# main.net
KiCad netlist of a schematic drawn in EAGLE
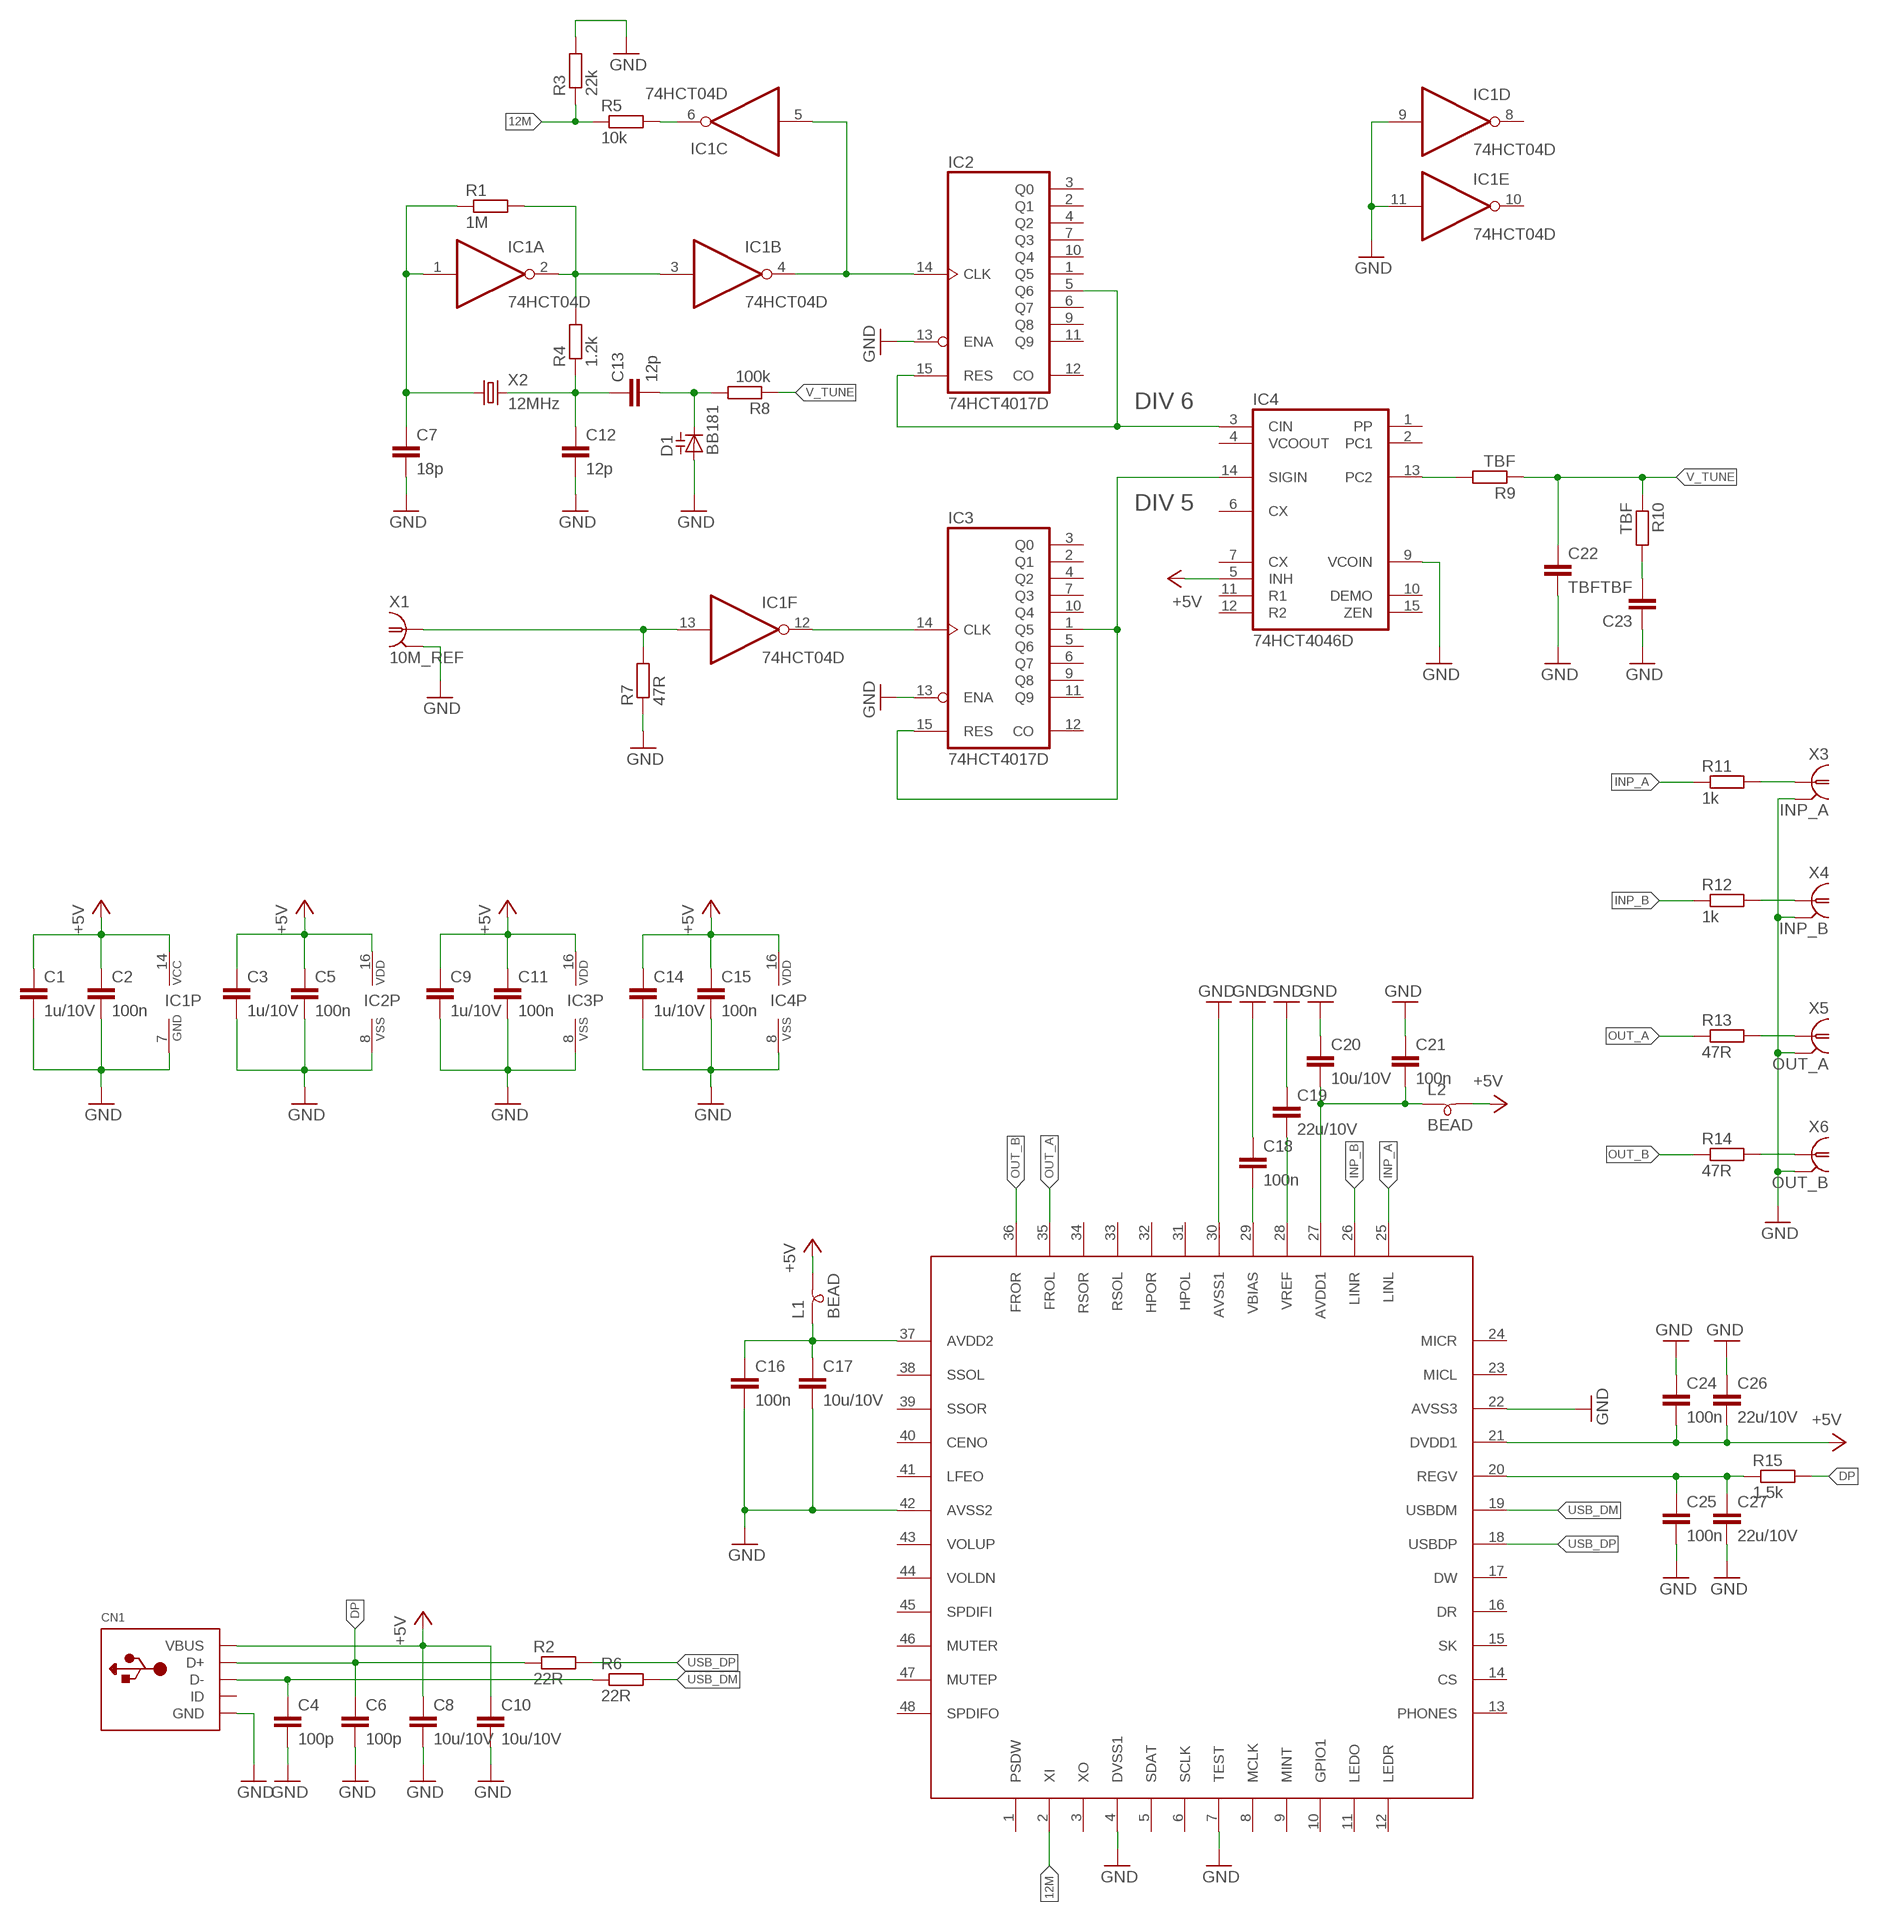
[diagram p0: schematic, sheet 1]

(export (version "E")
  (design (tool "Eeschema 10.0.6"))
  (components
    (comp (ref "C1")
      (value "1u/10V")
      (footprint "eagle-import:C0805")
      (libsource (lib "eagle-import") (part "C-EUC0805"))
    )
    (comp (ref "C2")
      (value "100n")
      (footprint "eagle-import:C0805")
      (libsource (lib "eagle-import") (part "C-EUC0805"))
    )
    (comp (ref "C3")
      (value "1u/10V")
      (footprint "eagle-import:C0805")
      (libsource (lib "eagle-import") (part "C-EUC0805"))
    )
    (comp (ref "C4")
      (value "100p")
      (footprint "eagle-import:C0805")
      (libsource (lib "eagle-import") (part "C-EUC0805"))
    )
    (comp (ref "C5")
      (value "100n")
      (footprint "eagle-import:C0805")
      (libsource (lib "eagle-import") (part "C-EUC0805"))
    )
    (comp (ref "C6")
      (value "100p")
      (footprint "eagle-import:C0805")
      (libsource (lib "eagle-import") (part "C-EUC0805"))
    )
    (comp (ref "C7")
      (value "18p")
      (footprint "eagle-import:C0805")
      (libsource (lib "eagle-import") (part "C-EUC0805"))
    )
    (comp (ref "C8")
      (value "10u/10V")
      (footprint "eagle-import:C1206")
      (libsource (lib "eagle-import") (part "C-EUC1206"))
    )
    (comp (ref "C9")
      (value "1u/10V")
      (footprint "eagle-import:C0805")
      (libsource (lib "eagle-import") (part "C-EUC0805"))
    )
    (comp (ref "C10")
      (value "10u/10V")
      (footprint "eagle-import:C1206")
      (libsource (lib "eagle-import") (part "C-EUC1206"))
    )
    (comp (ref "C11")
      (value "100n")
      (footprint "eagle-import:C0805")
      (libsource (lib "eagle-import") (part "C-EUC0805"))
    )
    (comp (ref "C12")
      (value "12p")
      (footprint "eagle-import:C0805")
      (libsource (lib "eagle-import") (part "C-EUC0805"))
    )
    (comp (ref "C13")
      (value "12p")
      (footprint "eagle-import:C0805")
      (libsource (lib "eagle-import") (part "C-EUC0805"))
    )
    (comp (ref "C14")
      (value "1u/10V")
      (footprint "eagle-import:C0805")
      (libsource (lib "eagle-import") (part "C-EUC0805"))
    )
    (comp (ref "C15")
      (value "100n")
      (footprint "eagle-import:C0805")
      (libsource (lib "eagle-import") (part "C-EUC0805"))
    )
    (comp (ref "C16")
      (value "100n")
      (footprint "eagle-import:C0805")
      (libsource (lib "eagle-import") (part "C-EUC0805"))
    )
    (comp (ref "C17")
      (value "10u/10V")
      (footprint "eagle-import:C0805")
      (libsource (lib "eagle-import") (part "C-EUC0805"))
    )
    (comp (ref "C18")
      (value "100n")
      (footprint "eagle-import:C0805")
      (libsource (lib "eagle-import") (part "C-EUC0805"))
    )
    (comp (ref "C19")
      (value "22u/10V")
      (footprint "eagle-import:C0805")
      (libsource (lib "eagle-import") (part "C-EUC0805"))
    )
    (comp (ref "C20")
      (value "10u/10V")
      (footprint "eagle-import:C0805")
      (libsource (lib "eagle-import") (part "C-EUC0805"))
    )
    (comp (ref "C21")
      (value "100n")
      (footprint "eagle-import:C0805")
      (libsource (lib "eagle-import") (part "C-EUC0805"))
    )
    (comp (ref "C22")
      (value "TBF")
      (footprint "eagle-import:C0805")
      (libsource (lib "eagle-import") (part "C-EUC0805"))
    )
    (comp (ref "C23")
      (value "TBF")
      (footprint "eagle-import:C0805")
      (libsource (lib "eagle-import") (part "C-EUC0805"))
    )
    (comp (ref "C24")
      (value "100n")
      (footprint "eagle-import:C0805")
      (libsource (lib "eagle-import") (part "C-EUC0805"))
    )
    (comp (ref "C25")
      (value "100n")
      (footprint "eagle-import:C0805")
      (libsource (lib "eagle-import") (part "C-EUC0805"))
    )
    (comp (ref "C26")
      (value "22u/10V")
      (footprint "eagle-import:C0805")
      (libsource (lib "eagle-import") (part "C-EUC0805"))
    )
    (comp (ref "C27")
      (value "22u/10V")
      (footprint "eagle-import:C0805")
      (libsource (lib "eagle-import") (part "C-EUC0805"))
    )
    (comp (ref "CN1")
      (value "USBMINIB")
      (footprint "eagle-import:USB-MINIB")
      (libsource (lib "eagle-import") (part "USBMINIB"))
    )
    (comp (ref "D1")
      (value "BB181")
      (footprint "eagle-import:SOD523")
      (libsource (lib "eagle-import") (part "BB141"))
    )
    (comp (ref "IC1")
      (value "74HCT04D")
      (footprint "eagle-import:SO14")
      (libsource (lib "eagle-import") (part "7404DHCT"))
    )
    (comp (ref "IC2")
      (value "74HCT4017D")
      (footprint "eagle-import:SO16")
      (libsource (lib "eagle-import") (part "4017D"))
    )
    (comp (ref "IC3")
      (value "74HCT4017D")
      (footprint "eagle-import:SO16")
      (libsource (lib "eagle-import") (part "4017D"))
    )
    (comp (ref "IC4")
      (value "74HCT4046D")
      (footprint "eagle-import:SO16")
      (libsource (lib "eagle-import") (part "4046D"))
    )
    (comp (ref "L1")
      (value "BEAD")
      (footprint "eagle-import:SM-B5")
      (libsource (lib "eagle-import") (part "SM-B5"))
    )
    (comp (ref "L2")
      (value "BEAD")
      (footprint "eagle-import:SM-B5")
      (libsource (lib "eagle-import") (part "SM-B5"))
    )
    (comp (ref "R1")
      (value "1M")
      (footprint "eagle-import:R0805")
      (libsource (lib "eagle-import") (part "R-EU_R0805"))
    )
    (comp (ref "R2")
      (value "22R")
      (footprint "eagle-import:R0805")
      (libsource (lib "eagle-import") (part "R-EU_R0805"))
    )
    (comp (ref "R3")
      (value "22k")
      (footprint "eagle-import:R0805")
      (libsource (lib "eagle-import") (part "R-EU_R0805"))
    )
    (comp (ref "R4")
      (value "1.2k")
      (footprint "eagle-import:R0805")
      (libsource (lib "eagle-import") (part "R-EU_R0805"))
    )
    (comp (ref "R5")
      (value "10k")
      (footprint "eagle-import:R0805")
      (libsource (lib "eagle-import") (part "R-EU_R0805"))
    )
    (comp (ref "R6")
      (value "22R")
      (footprint "eagle-import:R0805")
      (libsource (lib "eagle-import") (part "R-EU_R0805"))
    )
    (comp (ref "R7")
      (value "47R")
      (footprint "eagle-import:R0805")
      (libsource (lib "eagle-import") (part "R-EU_R0805"))
    )
    (comp (ref "R8")
      (value "100k")
      (footprint "eagle-import:R0805")
      (libsource (lib "eagle-import") (part "R-EU_R0805"))
    )
    (comp (ref "R9")
      (value "TBF")
      (footprint "eagle-import:R0805")
      (libsource (lib "eagle-import") (part "R-EU_R0805"))
    )
    (comp (ref "R10")
      (value "TBF")
      (footprint "eagle-import:R0805")
      (libsource (lib "eagle-import") (part "R-EU_R0805"))
    )
    (comp (ref "R11")
      (value "1k")
      (footprint "eagle-import:R0805")
      (libsource (lib "eagle-import") (part "R-EU_R0805"))
    )
    (comp (ref "R12")
      (value "1k")
      (footprint "eagle-import:R0805")
      (libsource (lib "eagle-import") (part "R-EU_R0805"))
    )
    (comp (ref "R13")
      (value "47R")
      (footprint "eagle-import:R0805")
      (libsource (lib "eagle-import") (part "R-EU_R0805"))
    )
    (comp (ref "R14")
      (value "47R")
      (footprint "eagle-import:R0805")
      (libsource (lib "eagle-import") (part "R-EU_R0805"))
    )
    (comp (ref "R15")
      (value "1.5k")
      (footprint "eagle-import:R0805")
      (libsource (lib "eagle-import") (part "R-EU_R0805"))
    )
    (comp (ref "U1")
      (value "CM6206")
      (footprint "eagle-import:LQFP-48")
      (libsource (lib "eagle-import") (part "CM6206"))
    )
    (comp (ref "X1")
      (value "10M_REF")
      (footprint "eagle-import:AMP_227161")
      (libsource (lib "eagle-import") (part "?2271611--2"))
    )
    (comp (ref "X2")
      (value "12MHz")
      (footprint "eagle-import:HC49")
      (libsource (lib "eagle-import") (part "CRYSTALS-NOGND-HC49/4H"))
    )
    (comp (ref "X3")
      (value "INP_A")
      (footprint "eagle-import:AMP_227161")
      (libsource (lib "eagle-import") (part "?2271611--2"))
    )
    (comp (ref "X4")
      (value "INP_B")
      (footprint "eagle-import:AMP_227161")
      (libsource (lib "eagle-import") (part "?2271611--2"))
    )
    (comp (ref "X5")
      (value "OUT_A")
      (footprint "eagle-import:AMP_227161")
      (libsource (lib "eagle-import") (part "?2271611--2"))
    )
    (comp (ref "X6")
      (value "OUT_B")
      (footprint "eagle-import:AMP_227161")
      (libsource (lib "eagle-import") (part "?2271611--2"))
    )
  )
  (nets
    (net (code "1") (name "+5V") (class "Default")
      (node (ref "C1") (pin "1") (pinfunction "1_1") (pintype "passive"))
      (node (ref "C10") (pin "1") (pinfunction "1_1") (pintype "passive"))
      (node (ref "C11") (pin "1") (pinfunction "1_1") (pintype "passive"))
      (node (ref "C14") (pin "1") (pinfunction "1_1") (pintype "passive"))
      (node (ref "C15") (pin "1") (pinfunction "1_1") (pintype "passive"))
      (node (ref "C2") (pin "1") (pinfunction "1_1") (pintype "passive"))
      (node (ref "C24") (pin "2") (pinfunction "2_2") (pintype "passive"))
      (node (ref "C26") (pin "2") (pinfunction "2_2") (pintype "passive"))
      (node (ref "C3") (pin "1") (pinfunction "1_1") (pintype "passive"))
      (node (ref "C5") (pin "1") (pinfunction "1_1") (pintype "passive"))
      (node (ref "C8") (pin "1") (pinfunction "1_1") (pintype "passive"))
      (node (ref "C9") (pin "1") (pinfunction "1_1") (pintype "passive"))
      (node (ref "CN1") (pin "VBUS") (pinfunction "VBUS_VBUS") (pintype "power_in"))
      (node (ref "IC1") (pin "14") (pinfunction "VCC_14") (pintype "power_in"))
      (node (ref "IC2") (pin "16") (pinfunction "VDD_16") (pintype "power_in"))
      (node (ref "IC3") (pin "16") (pinfunction "VDD_16") (pintype "power_in"))
      (node (ref "IC4") (pin "16") (pinfunction "VDD_16") (pintype "power_in"))
      (node (ref "IC4") (pin "5") (pinfunction "INH_5") (pintype "input"))
      (node (ref "L1") (pin "2") (pinfunction "2_2") (pintype "passive"))
      (node (ref "L2") (pin "2") (pinfunction "2_2") (pintype "passive"))
      (node (ref "U1") (pin "21") (pinfunction "DVDD1_21") (pintype "bidirectional"))
    )
    (net (code "2") (name "12M") (class "Default")
      (node (ref "R3") (pin "1") (pinfunction "1_1") (pintype "passive"))
      (node (ref "R5") (pin "1") (pinfunction "1_1") (pintype "passive"))
      (node (ref "U1") (pin "2") (pinfunction "XI_2") (pintype "bidirectional"))
    )
    (net (code "3") (name "DP") (class "Default")
      (node (ref "C6") (pin "1") (pinfunction "1_1") (pintype "passive"))
      (node (ref "CN1") (pin "D+") (pinfunction "D+_D+") (pintype "bidirectional"))
      (node (ref "R15") (pin "2") (pinfunction "2_2") (pintype "passive"))
      (node (ref "R2") (pin "1") (pinfunction "1_1") (pintype "passive"))
    )
    (net (code "4") (name "GND") (class "Default")
      (node (ref "C1") (pin "2") (pinfunction "2_2") (pintype "passive"))
      (node (ref "C10") (pin "2") (pinfunction "2_2") (pintype "passive"))
      (node (ref "C11") (pin "2") (pinfunction "2_2") (pintype "passive"))
      (node (ref "C12") (pin "2") (pinfunction "2_2") (pintype "passive"))
      (node (ref "C14") (pin "2") (pinfunction "2_2") (pintype "passive"))
      (node (ref "C15") (pin "2") (pinfunction "2_2") (pintype "passive"))
      (node (ref "C16") (pin "2") (pinfunction "2_2") (pintype "passive"))
      (node (ref "C17") (pin "2") (pinfunction "2_2") (pintype "passive"))
      (node (ref "C18") (pin "1") (pinfunction "1_1") (pintype "passive"))
      (node (ref "C19") (pin "1") (pinfunction "1_1") (pintype "passive"))
      (node (ref "C2") (pin "2") (pinfunction "2_2") (pintype "passive"))
      (node (ref "C20") (pin "1") (pinfunction "1_1") (pintype "passive"))
      (node (ref "C21") (pin "1") (pinfunction "1_1") (pintype "passive"))
      (node (ref "C22") (pin "2") (pinfunction "2_2") (pintype "passive"))
      (node (ref "C23") (pin "1") (pinfunction "1_1") (pintype "passive"))
      (node (ref "C24") (pin "1") (pinfunction "1_1") (pintype "passive"))
      (node (ref "C25") (pin "2") (pinfunction "2_2") (pintype "passive"))
      (node (ref "C26") (pin "1") (pinfunction "1_1") (pintype "passive"))
      (node (ref "C27") (pin "2") (pinfunction "2_2") (pintype "passive"))
      (node (ref "C3") (pin "2") (pinfunction "2_2") (pintype "passive"))
      (node (ref "C4") (pin "2") (pinfunction "2_2") (pintype "passive"))
      (node (ref "C5") (pin "2") (pinfunction "2_2") (pintype "passive"))
      (node (ref "C6") (pin "2") (pinfunction "2_2") (pintype "passive"))
      (node (ref "C7") (pin "2") (pinfunction "2_2") (pintype "passive"))
      (node (ref "C8") (pin "2") (pinfunction "2_2") (pintype "passive"))
      (node (ref "C9") (pin "2") (pinfunction "2_2") (pintype "passive"))
      (node (ref "CN1") (pin "GND") (pinfunction "GND_GND") (pintype "power_in"))
      (node (ref "D1") (pin "A") (pinfunction "A_A") (pintype "passive"))
      (node (ref "IC1") (pin "11") (pinfunction "I_11") (pintype "input"))
      (node (ref "IC1") (pin "7") (pinfunction "GND_7") (pintype "power_in"))
      (node (ref "IC1") (pin "9") (pinfunction "I_9") (pintype "input"))
      (node (ref "IC2") (pin "13") (pinfunction "ENA_13") (pintype "input"))
      (node (ref "IC2") (pin "8") (pinfunction "VSS_8") (pintype "power_in"))
      (node (ref "IC3") (pin "13") (pinfunction "ENA_13") (pintype "input"))
      (node (ref "IC3") (pin "8") (pinfunction "VSS_8") (pintype "power_in"))
      (node (ref "IC4") (pin "8") (pinfunction "VSS_8") (pintype "power_in"))
      (node (ref "IC4") (pin "9") (pinfunction "VCOIN_9") (pintype "input"))
      (node (ref "R3") (pin "2") (pinfunction "2_2") (pintype "passive"))
      (node (ref "R7") (pin "1") (pinfunction "1_1") (pintype "passive"))
      (node (ref "U1") (pin "22") (pinfunction "AVSS3_22") (pintype "bidirectional"))
      (node (ref "U1") (pin "30") (pinfunction "AVSS1_30") (pintype "bidirectional"))
      (node (ref "U1") (pin "4") (pinfunction "DVSS1_4") (pintype "bidirectional"))
      (node (ref "U1") (pin "42") (pinfunction "AVSS2_42") (pintype "bidirectional"))
      (node (ref "U1") (pin "7") (pinfunction "TEST_7") (pintype "bidirectional"))
      (node (ref "X1") (pin "2") (pinfunction "2_2") (pintype "passive"))
      (node (ref "X3") (pin "2") (pinfunction "2_2") (pintype "passive"))
      (node (ref "X4") (pin "2") (pinfunction "2_2") (pintype "passive"))
      (node (ref "X5") (pin "2") (pinfunction "2_2") (pintype "passive"))
      (node (ref "X6") (pin "2") (pinfunction "2_2") (pintype "passive"))
    )
    (net (code "5") (name "INP_A") (class "Default")
      (node (ref "R11") (pin "1") (pinfunction "1_1") (pintype "passive"))
      (node (ref "U1") (pin "25") (pinfunction "LINL_25") (pintype "bidirectional"))
    )
    (net (code "6") (name "INP_B") (class "Default")
      (node (ref "R12") (pin "1") (pinfunction "1_1") (pintype "passive"))
      (node (ref "U1") (pin "26") (pinfunction "LINR_26") (pintype "bidirectional"))
    )
    (net (code "7") (name "Net-(C4-Pad1)") (class "Default")
      (node (ref "C4") (pin "1") (pinfunction "1_1") (pintype "passive"))
      (node (ref "CN1") (pin "D-") (pinfunction "D-_D-") (pintype "bidirectional"))
      (node (ref "R6") (pin "1") (pinfunction "1_1") (pintype "passive"))
    )
    (net (code "8") (name "Net-(C12-Pad1)") (class "Default")
      (node (ref "C12") (pin "1") (pinfunction "1_1") (pintype "passive"))
      (node (ref "C13") (pin "1") (pinfunction "1_1") (pintype "passive"))
      (node (ref "R4") (pin "1") (pinfunction "1_1") (pintype "passive"))
      (node (ref "X2") (pin "2") (pinfunction "2_2") (pintype "passive"))
    )
    (net (code "9") (name "Net-(C13-Pad2)") (class "Default")
      (node (ref "C13") (pin "2") (pinfunction "2_2") (pintype "passive"))
      (node (ref "D1") (pin "C") (pinfunction "C_C") (pintype "passive"))
      (node (ref "R8") (pin "2") (pinfunction "2_2") (pintype "passive"))
    )
    (net (code "10") (name "Net-(C23-Pad2)") (class "Default")
      (node (ref "C23") (pin "2") (pinfunction "2_2") (pintype "passive"))
      (node (ref "R10") (pin "2") (pinfunction "2_2") (pintype "passive"))
    )
    (net (code "11") (name "Net-(IC1A-I)") (class "Default")
      (node (ref "C7") (pin "1") (pinfunction "1_1") (pintype "passive"))
      (node (ref "IC1") (pin "1") (pinfunction "I_1") (pintype "input"))
      (node (ref "R1") (pin "1") (pinfunction "1_1") (pintype "passive"))
      (node (ref "X2") (pin "1") (pinfunction "1_1") (pintype "passive"))
    )
    (net (code "12") (name "Net-(IC1A-O)") (class "Default")
      (node (ref "IC1") (pin "2") (pinfunction "O_2") (pintype "output"))
      (node (ref "IC1") (pin "3") (pinfunction "I_3") (pintype "input"))
      (node (ref "R1") (pin "2") (pinfunction "2_2") (pintype "passive"))
      (node (ref "R4") (pin "2") (pinfunction "2_2") (pintype "passive"))
    )
    (net (code "13") (name "Net-(IC1B-O)") (class "Default")
      (node (ref "IC1") (pin "4") (pinfunction "O_4") (pintype "output"))
      (node (ref "IC1") (pin "5") (pinfunction "I_5") (pintype "input"))
      (node (ref "IC2") (pin "14") (pinfunction "CLK_14") (pintype "input"))
    )
    (net (code "14") (name "Net-(IC1C-O)") (class "Default")
      (node (ref "IC1") (pin "6") (pinfunction "O_6") (pintype "output"))
      (node (ref "R5") (pin "2") (pinfunction "2_2") (pintype "passive"))
    )
    (net (code "15") (name "Net-(IC1F-I)") (class "Default")
      (node (ref "IC1") (pin "13") (pinfunction "I_13") (pintype "input"))
      (node (ref "R7") (pin "2") (pinfunction "2_2") (pintype "passive"))
      (node (ref "X1") (pin "1") (pinfunction "1_1") (pintype "passive"))
    )
    (net (code "16") (name "Net-(IC1F-O)") (class "Default")
      (node (ref "IC1") (pin "12") (pinfunction "O_12") (pintype "output"))
      (node (ref "IC3") (pin "14") (pinfunction "CLK_14") (pintype "input"))
    )
    (net (code "17") (name "Net-(IC2A-Q6)") (class "Default")
      (node (ref "IC2") (pin "15") (pinfunction "RES_15") (pintype "input"))
      (node (ref "IC2") (pin "5") (pinfunction "Q6_5") (pintype "output"))
      (node (ref "IC4") (pin "3") (pinfunction "CIN_3") (pintype "input"))
    )
    (net (code "18") (name "Net-(IC3A-Q5)") (class "Default")
      (node (ref "IC3") (pin "1") (pinfunction "Q5_1") (pintype "output"))
      (node (ref "IC3") (pin "15") (pinfunction "RES_15") (pintype "input"))
      (node (ref "IC4") (pin "14") (pinfunction "SIGIN_14") (pintype "input"))
    )
    (net (code "19") (name "Net-(IC4A-PC2)") (class "Default")
      (node (ref "IC4") (pin "13") (pinfunction "PC2_13") (pintype "output"))
      (node (ref "R9") (pin "2") (pinfunction "2_2") (pintype "passive"))
    )
    (net (code "20") (name "Net-(R11-Pad2)") (class "Default")
      (node (ref "R11") (pin "2") (pinfunction "2_2") (pintype "passive"))
      (node (ref "X3") (pin "1") (pinfunction "1_1") (pintype "passive"))
    )
    (net (code "21") (name "Net-(R12-Pad2)") (class "Default")
      (node (ref "R12") (pin "2") (pinfunction "2_2") (pintype "passive"))
      (node (ref "X4") (pin "1") (pinfunction "1_1") (pintype "passive"))
    )
    (net (code "22") (name "Net-(R13-Pad2)") (class "Default")
      (node (ref "R13") (pin "2") (pinfunction "2_2") (pintype "passive"))
      (node (ref "X5") (pin "1") (pinfunction "1_1") (pintype "passive"))
    )
    (net (code "23") (name "Net-(R14-Pad2)") (class "Default")
      (node (ref "R14") (pin "2") (pinfunction "2_2") (pintype "passive"))
      (node (ref "X6") (pin "1") (pinfunction "1_1") (pintype "passive"))
    )
    (net (code "24") (name "Net-(U1-AVDD1)") (class "Default")
      (node (ref "C20") (pin "2") (pinfunction "2_2") (pintype "passive"))
      (node (ref "C21") (pin "2") (pinfunction "2_2") (pintype "passive"))
      (node (ref "L2") (pin "1") (pinfunction "1_1") (pintype "passive"))
      (node (ref "U1") (pin "27") (pinfunction "AVDD1_27") (pintype "bidirectional"))
    )
    (net (code "25") (name "Net-(U1-AVDD2)") (class "Default")
      (node (ref "C16") (pin "1") (pinfunction "1_1") (pintype "passive"))
      (node (ref "C17") (pin "1") (pinfunction "1_1") (pintype "passive"))
      (node (ref "L1") (pin "1") (pinfunction "1_1") (pintype "passive"))
      (node (ref "U1") (pin "37") (pinfunction "AVDD2_37") (pintype "bidirectional"))
    )
    (net (code "26") (name "Net-(U1-REGV)") (class "Default")
      (node (ref "C25") (pin "1") (pinfunction "1_1") (pintype "passive"))
      (node (ref "C27") (pin "1") (pinfunction "1_1") (pintype "passive"))
      (node (ref "R15") (pin "1") (pinfunction "1_1") (pintype "passive"))
      (node (ref "U1") (pin "20") (pinfunction "REGV_20") (pintype "bidirectional"))
    )
    (net (code "27") (name "Net-(U1-VBIAS)") (class "Default")
      (node (ref "C18") (pin "2") (pinfunction "2_2") (pintype "passive"))
      (node (ref "U1") (pin "29") (pinfunction "VBIAS_29") (pintype "bidirectional"))
    )
    (net (code "28") (name "Net-(U1-VREF)") (class "Default")
      (node (ref "C19") (pin "2") (pinfunction "2_2") (pintype "passive"))
      (node (ref "U1") (pin "28") (pinfunction "VREF_28") (pintype "bidirectional"))
    )
    (net (code "29") (name "OUT_A") (class "Default")
      (node (ref "R13") (pin "1") (pinfunction "1_1") (pintype "passive"))
      (node (ref "U1") (pin "35") (pinfunction "FROL_35") (pintype "bidirectional"))
    )
    (net (code "30") (name "OUT_B") (class "Default")
      (node (ref "R14") (pin "1") (pinfunction "1_1") (pintype "passive"))
      (node (ref "U1") (pin "36") (pinfunction "FROR_36") (pintype "bidirectional"))
    )
    (net (code "31") (name "USB_DM") (class "Default")
      (node (ref "R6") (pin "2") (pinfunction "2_2") (pintype "passive"))
      (node (ref "U1") (pin "19") (pinfunction "USBDM_19") (pintype "bidirectional"))
    )
    (net (code "32") (name "USB_DP") (class "Default")
      (node (ref "R2") (pin "2") (pinfunction "2_2") (pintype "passive"))
      (node (ref "U1") (pin "18") (pinfunction "USBDP_18") (pintype "bidirectional"))
    )
    (net (code "33") (name "V_TUNE") (class "Default")
      (node (ref "C22") (pin "1") (pinfunction "1_1") (pintype "passive"))
      (node (ref "R10") (pin "1") (pinfunction "1_1") (pintype "passive"))
      (node (ref "R8") (pin "1") (pinfunction "1_1") (pintype "passive"))
      (node (ref "R9") (pin "1") (pinfunction "1_1") (pintype "passive"))
    )
    (net (code "34") (name "unconnected-(CN1-PadID)") (class "Default")
      (node (ref "CN1") (pin "ID") (pinfunction "ID_ID") (pintype "bidirectional"))
    )
    (net (code "35") (name "unconnected-(IC1D-O-Pad8)") (class "Default")
      (node (ref "IC1") (pin "8") (pinfunction "O_8") (pintype "output"))
    )
    (net (code "36") (name "unconnected-(IC1E-O-Pad10)") (class "Default")
      (node (ref "IC1") (pin "10") (pinfunction "O_10") (pintype "output"))
    )
    (net (code "37") (name "unconnected-(IC2A-CO-Pad12)") (class "Default")
      (node (ref "IC2") (pin "12") (pinfunction "CO_12") (pintype "output"))
    )
    (net (code "38") (name "unconnected-(IC2A-Q0-Pad3)") (class "Default")
      (node (ref "IC2") (pin "3") (pinfunction "Q0_3") (pintype "output"))
    )
    (net (code "39") (name "unconnected-(IC2A-Q1-Pad2)") (class "Default")
      (node (ref "IC2") (pin "2") (pinfunction "Q1_2") (pintype "output"))
    )
    (net (code "40") (name "unconnected-(IC2A-Q2-Pad4)") (class "Default")
      (node (ref "IC2") (pin "4") (pinfunction "Q2_4") (pintype "output"))
    )
    (net (code "41") (name "unconnected-(IC2A-Q3-Pad7)") (class "Default")
      (node (ref "IC2") (pin "7") (pinfunction "Q3_7") (pintype "output"))
    )
    (net (code "42") (name "unconnected-(IC2A-Q4-Pad10)") (class "Default")
      (node (ref "IC2") (pin "10") (pinfunction "Q4_10") (pintype "output"))
    )
    (net (code "43") (name "unconnected-(IC2A-Q5-Pad1)") (class "Default")
      (node (ref "IC2") (pin "1") (pinfunction "Q5_1") (pintype "output"))
    )
    (net (code "44") (name "unconnected-(IC2A-Q7-Pad6)") (class "Default")
      (node (ref "IC2") (pin "6") (pinfunction "Q7_6") (pintype "output"))
    )
    (net (code "45") (name "unconnected-(IC2A-Q8-Pad9)") (class "Default")
      (node (ref "IC2") (pin "9") (pinfunction "Q8_9") (pintype "output"))
    )
    (net (code "46") (name "unconnected-(IC2A-Q9-Pad11)") (class "Default")
      (node (ref "IC2") (pin "11") (pinfunction "Q9_11") (pintype "output"))
    )
    (net (code "47") (name "unconnected-(IC3A-CO-Pad12)") (class "Default")
      (node (ref "IC3") (pin "12") (pinfunction "CO_12") (pintype "output"))
    )
    (net (code "48") (name "unconnected-(IC3A-Q0-Pad3)") (class "Default")
      (node (ref "IC3") (pin "3") (pinfunction "Q0_3") (pintype "output"))
    )
    (net (code "49") (name "unconnected-(IC3A-Q1-Pad2)") (class "Default")
      (node (ref "IC3") (pin "2") (pinfunction "Q1_2") (pintype "output"))
    )
    (net (code "50") (name "unconnected-(IC3A-Q2-Pad4)") (class "Default")
      (node (ref "IC3") (pin "4") (pinfunction "Q2_4") (pintype "output"))
    )
    (net (code "51") (name "unconnected-(IC3A-Q3-Pad7)") (class "Default")
      (node (ref "IC3") (pin "7") (pinfunction "Q3_7") (pintype "output"))
    )
    (net (code "52") (name "unconnected-(IC3A-Q4-Pad10)") (class "Default")
      (node (ref "IC3") (pin "10") (pinfunction "Q4_10") (pintype "output"))
    )
    (net (code "53") (name "unconnected-(IC3A-Q6-Pad5)") (class "Default")
      (node (ref "IC3") (pin "5") (pinfunction "Q6_5") (pintype "output"))
    )
    (net (code "54") (name "unconnected-(IC3A-Q7-Pad6)") (class "Default")
      (node (ref "IC3") (pin "6") (pinfunction "Q7_6") (pintype "output"))
    )
    (net (code "55") (name "unconnected-(IC3A-Q8-Pad9)") (class "Default")
      (node (ref "IC3") (pin "9") (pinfunction "Q8_9") (pintype "output"))
    )
    (net (code "56") (name "unconnected-(IC3A-Q9-Pad11)") (class "Default")
      (node (ref "IC3") (pin "11") (pinfunction "Q9_11") (pintype "output"))
    )
    (net (code "57") (name "unconnected-(IC4A-CX-Pad6)") (class "Default")
      (node (ref "IC4") (pin "6") (pinfunction "CX_6") (pintype "input"))
    )
    (net (code "58") (name "unconnected-(IC4A-CX-Pad7)") (class "Default")
      (node (ref "IC4") (pin "7") (pinfunction "CX_7") (pintype "input"))
    )
    (net (code "59") (name "unconnected-(IC4A-DEMO-Pad10)") (class "Default")
      (node (ref "IC4") (pin "10") (pinfunction "DEMO_10") (pintype "output"))
    )
    (net (code "60") (name "unconnected-(IC4A-PC1-Pad2)") (class "Default")
      (node (ref "IC4") (pin "2") (pinfunction "PC1_2") (pintype "output"))
    )
    (net (code "61") (name "unconnected-(IC4A-PP-Pad1)") (class "Default")
      (node (ref "IC4") (pin "1") (pinfunction "PP_1") (pintype "output"))
    )
    (net (code "62") (name "unconnected-(IC4A-R1-Pad11)") (class "Default")
      (node (ref "IC4") (pin "11") (pinfunction "R1_11") (pintype "input"))
    )
    (net (code "63") (name "unconnected-(IC4A-R2-Pad12)") (class "Default")
      (node (ref "IC4") (pin "12") (pinfunction "R2_12") (pintype "input"))
    )
    (net (code "64") (name "unconnected-(IC4A-VCOOUT-Pad4)") (class "Default")
      (node (ref "IC4") (pin "4") (pinfunction "VCOOUT_4") (pintype "output"))
    )
    (net (code "65") (name "unconnected-(IC4A-ZEN-Pad15)") (class "Default")
      (node (ref "IC4") (pin "15") (pinfunction "ZEN_15") (pintype "input"))
    )
    (net (code "66") (name "unconnected-(U1-CENO-Pad40)") (class "Default")
      (node (ref "U1") (pin "40") (pinfunction "CENO_40") (pintype "bidirectional"))
    )
    (net (code "67") (name "unconnected-(U1-CS-Pad14)") (class "Default")
      (node (ref "U1") (pin "14") (pinfunction "CS_14") (pintype "bidirectional"))
    )
    (net (code "68") (name "unconnected-(U1-DR-Pad16)") (class "Default")
      (node (ref "U1") (pin "16") (pinfunction "DR_16") (pintype "bidirectional"))
    )
    (net (code "69") (name "unconnected-(U1-DW-Pad17)") (class "Default")
      (node (ref "U1") (pin "17") (pinfunction "DW_17") (pintype "bidirectional"))
    )
    (net (code "70") (name "unconnected-(U1-GPIO1-Pad10)") (class "Default")
      (node (ref "U1") (pin "10") (pinfunction "GPIO1_10") (pintype "bidirectional"))
    )
    (net (code "71") (name "unconnected-(U1-HPOL-Pad31)") (class "Default")
      (node (ref "U1") (pin "31") (pinfunction "HPOL_31") (pintype "bidirectional"))
    )
    (net (code "72") (name "unconnected-(U1-HPOR-Pad32)") (class "Default")
      (node (ref "U1") (pin "32") (pinfunction "HPOR_32") (pintype "bidirectional"))
    )
    (net (code "73") (name "unconnected-(U1-LEDO-Pad11)") (class "Default")
      (node (ref "U1") (pin "11") (pinfunction "LEDO_11") (pintype "bidirectional"))
    )
    (net (code "74") (name "unconnected-(U1-LEDR-Pad12)") (class "Default")
      (node (ref "U1") (pin "12") (pinfunction "LEDR_12") (pintype "bidirectional"))
    )
    (net (code "75") (name "unconnected-(U1-LFEO-Pad41)") (class "Default")
      (node (ref "U1") (pin "41") (pinfunction "LFEO_41") (pintype "bidirectional"))
    )
    (net (code "76") (name "unconnected-(U1-MCLK-Pad8)") (class "Default")
      (node (ref "U1") (pin "8") (pinfunction "MCLK_8") (pintype "bidirectional"))
    )
    (net (code "77") (name "unconnected-(U1-MICL-Pad23)") (class "Default")
      (node (ref "U1") (pin "23") (pinfunction "MICL_23") (pintype "bidirectional"))
    )
    (net (code "78") (name "unconnected-(U1-MICR-Pad24)") (class "Default")
      (node (ref "U1") (pin "24") (pinfunction "MICR_24") (pintype "bidirectional"))
    )
    (net (code "79") (name "unconnected-(U1-MINT-Pad9)") (class "Default")
      (node (ref "U1") (pin "9") (pinfunction "MINT_9") (pintype "bidirectional"))
    )
    (net (code "80") (name "unconnected-(U1-MUTEP-Pad47)") (class "Default")
      (node (ref "U1") (pin "47") (pinfunction "MUTEP_47") (pintype "bidirectional"))
    )
    (net (code "81") (name "unconnected-(U1-MUTER-Pad46)") (class "Default")
      (node (ref "U1") (pin "46") (pinfunction "MUTER_46") (pintype "bidirectional"))
    )
    (net (code "82") (name "unconnected-(U1-PHONES-Pad13)") (class "Default")
      (node (ref "U1") (pin "13") (pinfunction "PHONES_13") (pintype "bidirectional"))
    )
    (net (code "83") (name "unconnected-(U1-PSDW-Pad1)") (class "Default")
      (node (ref "U1") (pin "1") (pinfunction "PSDW_1") (pintype "bidirectional"))
    )
    (net (code "84") (name "unconnected-(U1-RSOL-Pad33)") (class "Default")
      (node (ref "U1") (pin "33") (pinfunction "RSOL_33") (pintype "bidirectional"))
    )
    (net (code "85") (name "unconnected-(U1-RSOR-Pad34)") (class "Default")
      (node (ref "U1") (pin "34") (pinfunction "RSOR_34") (pintype "bidirectional"))
    )
    (net (code "86") (name "unconnected-(U1-SCLK-Pad6)") (class "Default")
      (node (ref "U1") (pin "6") (pinfunction "SCLK_6") (pintype "bidirectional"))
    )
    (net (code "87") (name "unconnected-(U1-SDAT-Pad5)") (class "Default")
      (node (ref "U1") (pin "5") (pinfunction "SDAT_5") (pintype "bidirectional"))
    )
    (net (code "88") (name "unconnected-(U1-SK-Pad15)") (class "Default")
      (node (ref "U1") (pin "15") (pinfunction "SK_15") (pintype "bidirectional"))
    )
    (net (code "89") (name "unconnected-(U1-SPDIFI-Pad45)") (class "Default")
      (node (ref "U1") (pin "45") (pinfunction "SPDIFI_45") (pintype "bidirectional"))
    )
    (net (code "90") (name "unconnected-(U1-SPDIFO-Pad48)") (class "Default")
      (node (ref "U1") (pin "48") (pinfunction "SPDIFO_48") (pintype "bidirectional"))
    )
    (net (code "91") (name "unconnected-(U1-SSOL-Pad38)") (class "Default")
      (node (ref "U1") (pin "38") (pinfunction "SSOL_38") (pintype "bidirectional"))
    )
    (net (code "92") (name "unconnected-(U1-SSOR-Pad39)") (class "Default")
      (node (ref "U1") (pin "39") (pinfunction "SSOR_39") (pintype "bidirectional"))
    )
    (net (code "93") (name "unconnected-(U1-VOLDN-Pad44)") (class "Default")
      (node (ref "U1") (pin "44") (pinfunction "VOLDN_44") (pintype "bidirectional"))
    )
    (net (code "94") (name "unconnected-(U1-VOLUP-Pad43)") (class "Default")
      (node (ref "U1") (pin "43") (pinfunction "VOLUP_43") (pintype "bidirectional"))
    )
    (net (code "95") (name "unconnected-(U1-XO-Pad3)") (class "Default")
      (node (ref "U1") (pin "3") (pinfunction "XO_3") (pintype "bidirectional"))
    )
  )
)
